# hybrid_lower_pcb3_2.net
KiCad netlist of a schematic drawn in EAGLE
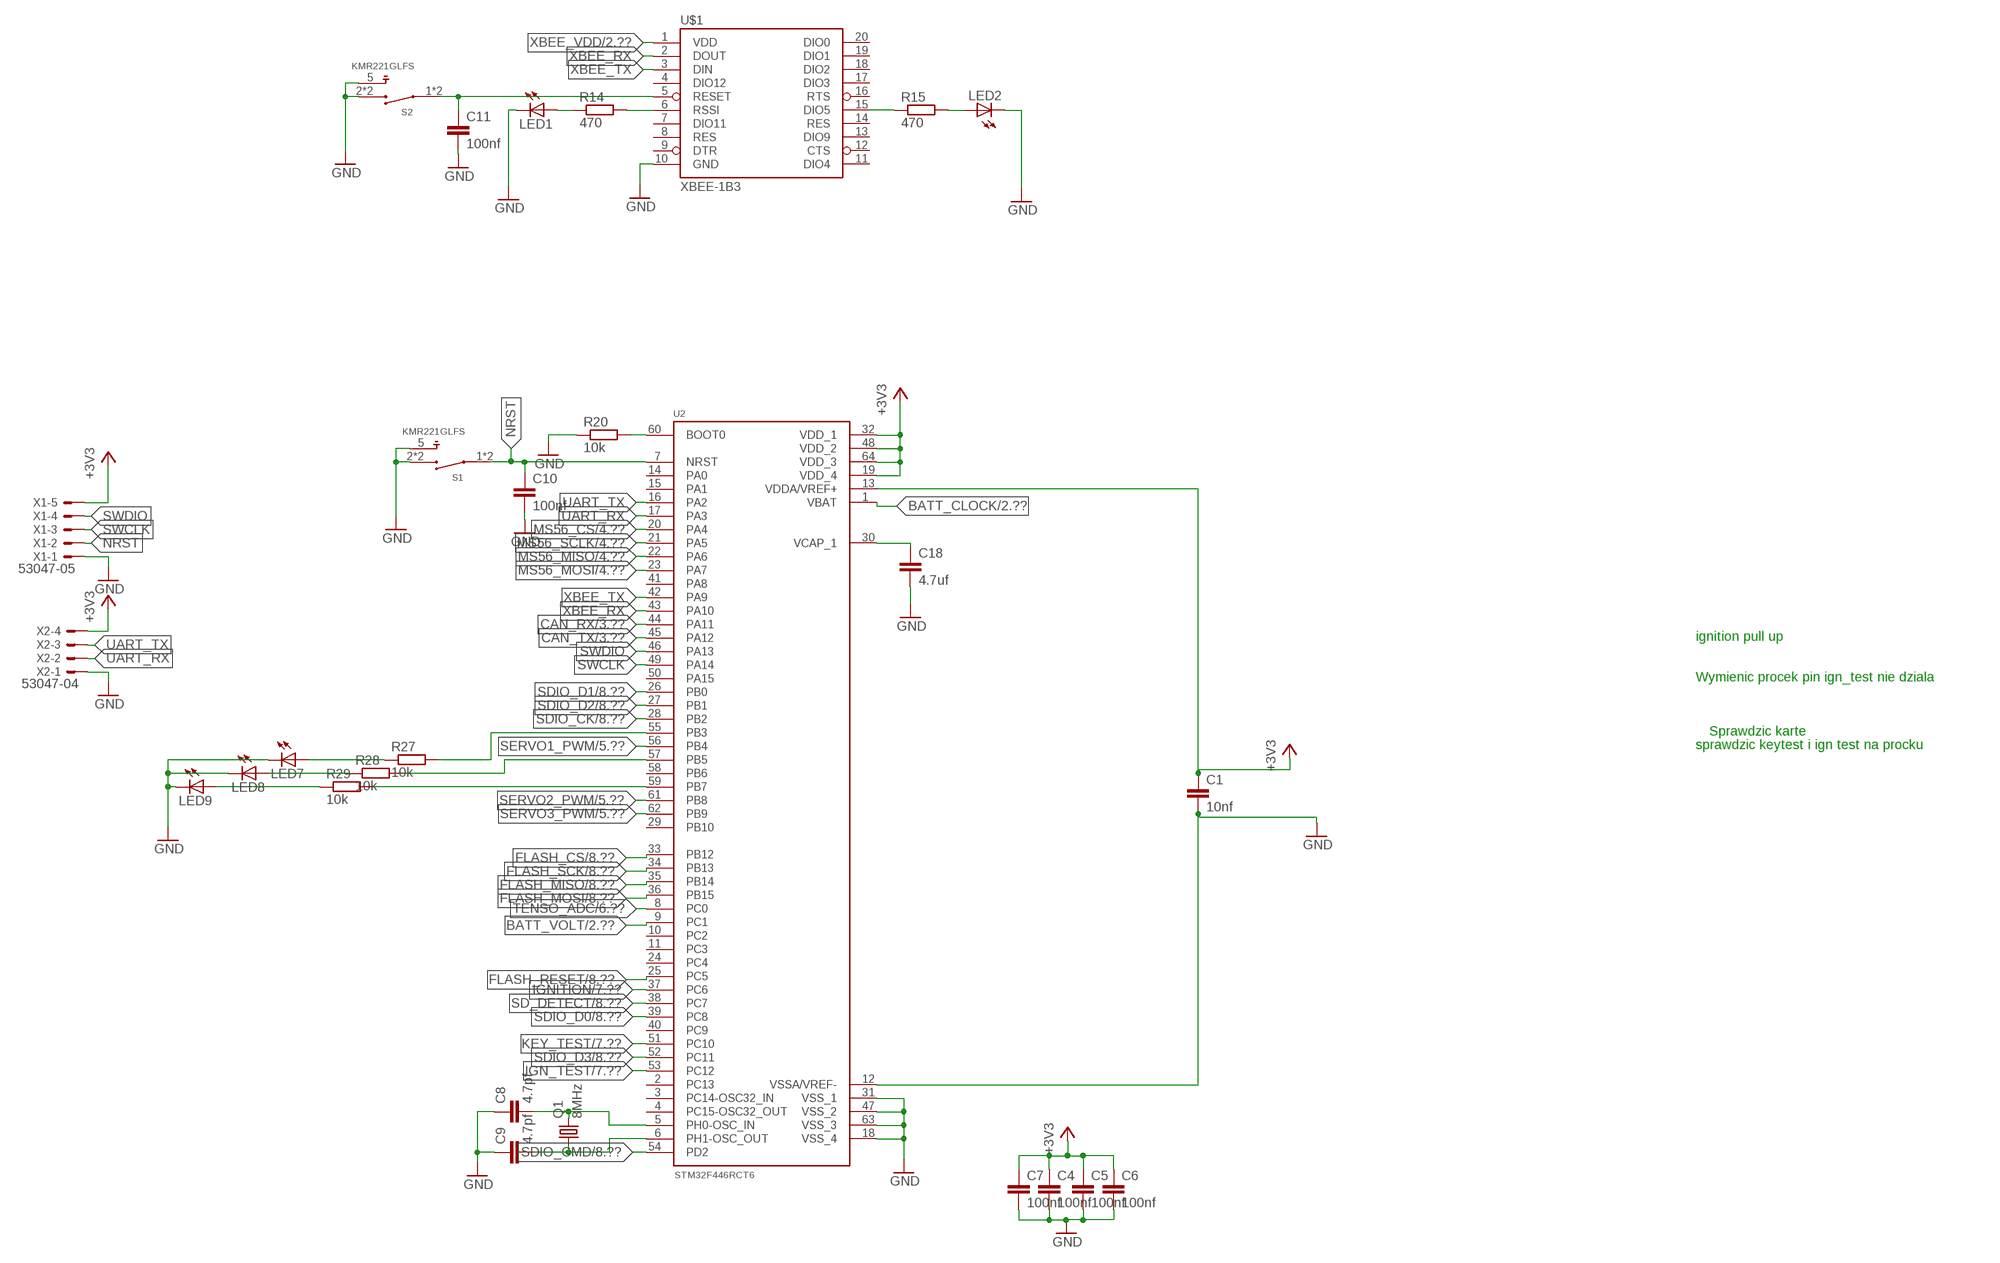
[diagram p0: schematic, sheet 1]
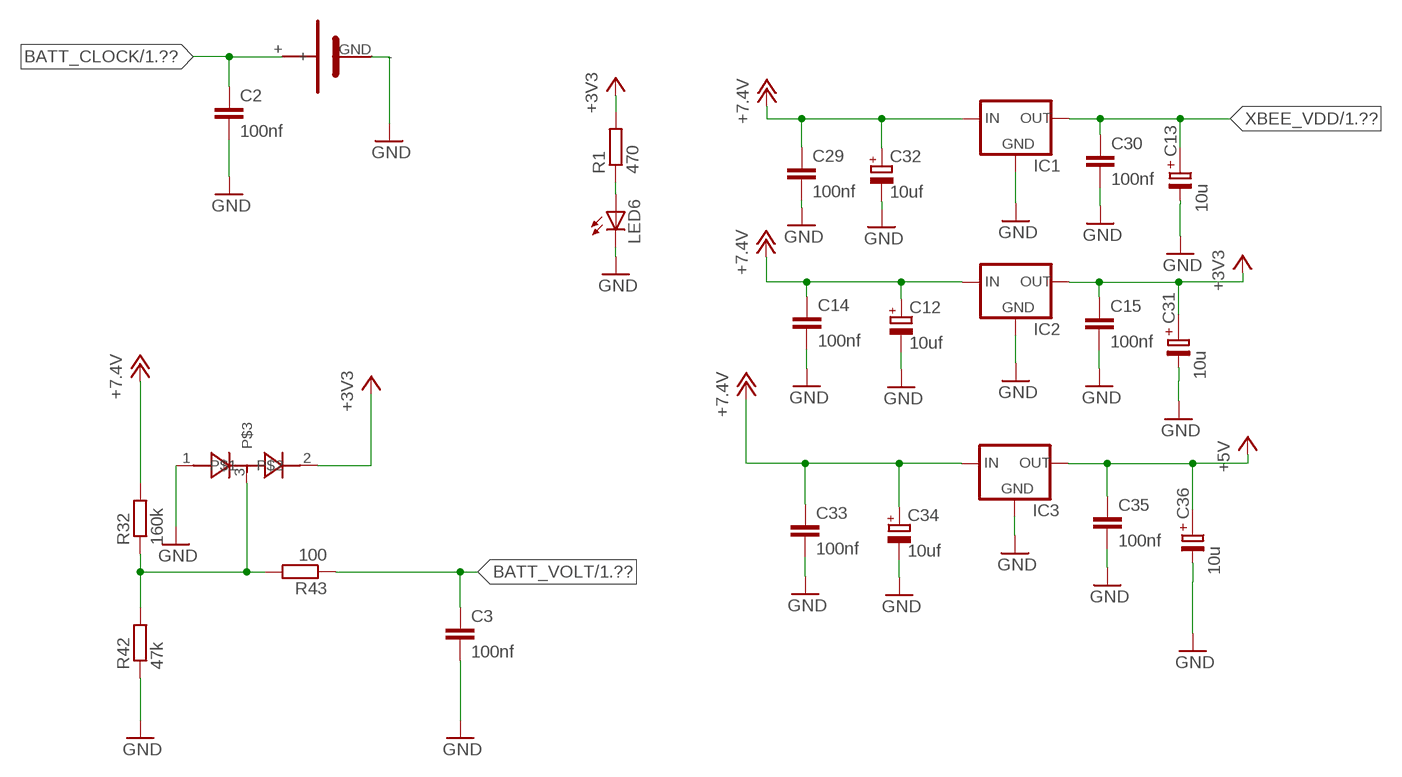
[diagram p1: schematic, sheet 2]
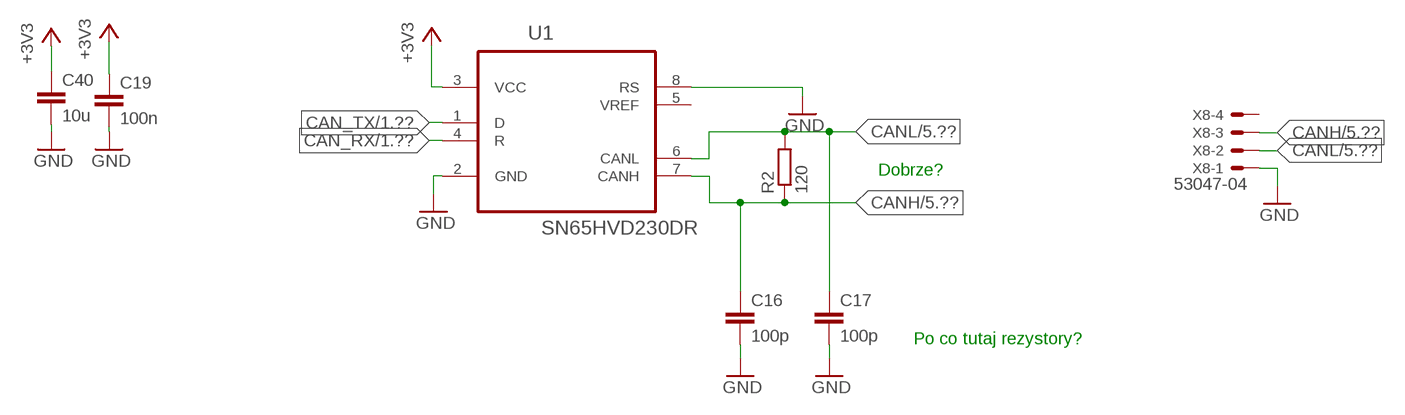
[diagram p2: schematic, sheet 3]
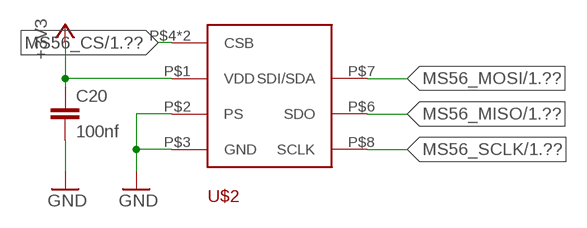
[diagram p3: schematic, sheet 4]
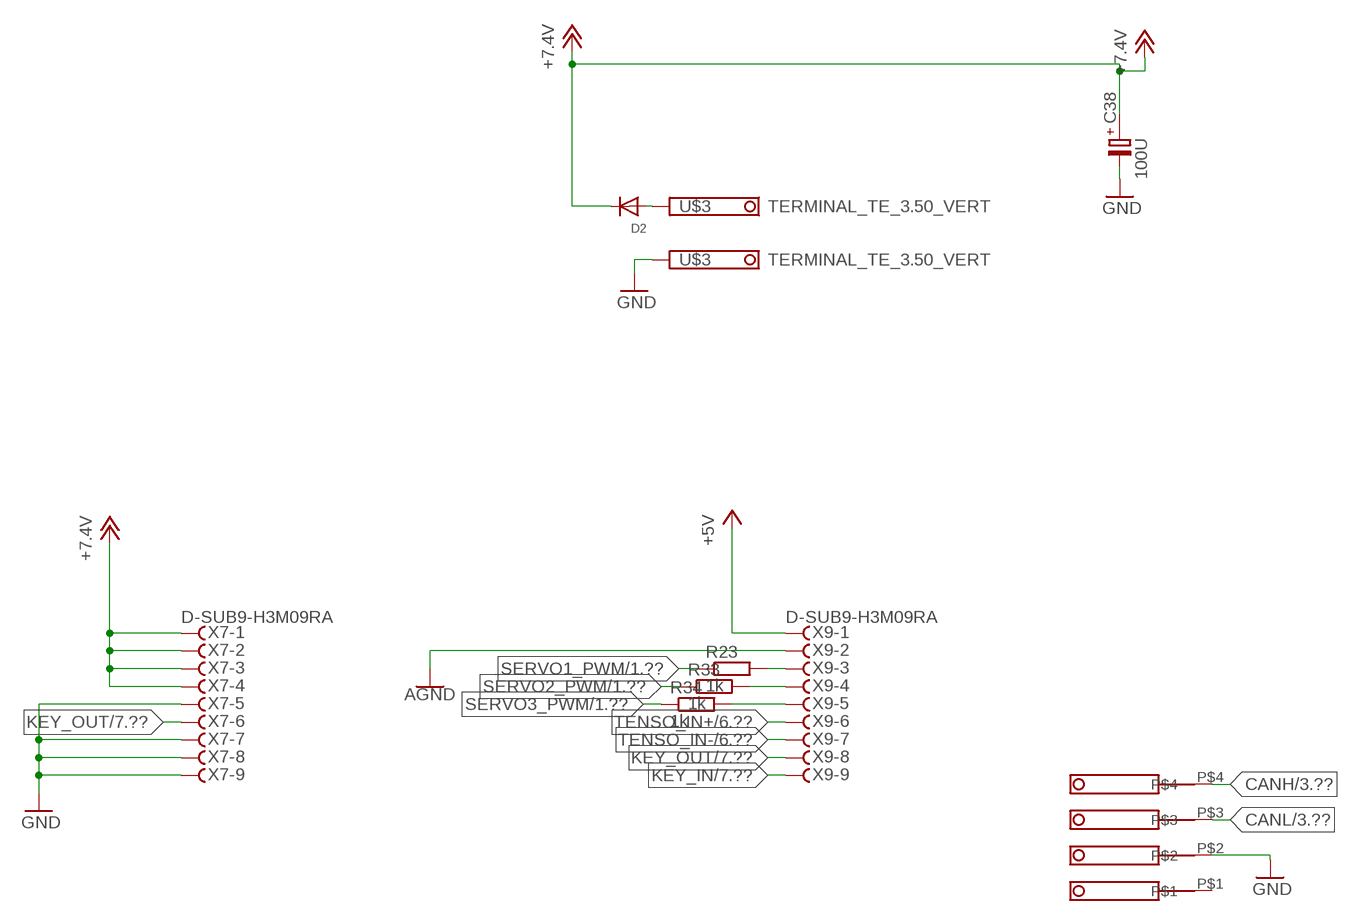
[diagram p4: schematic, sheet 5]
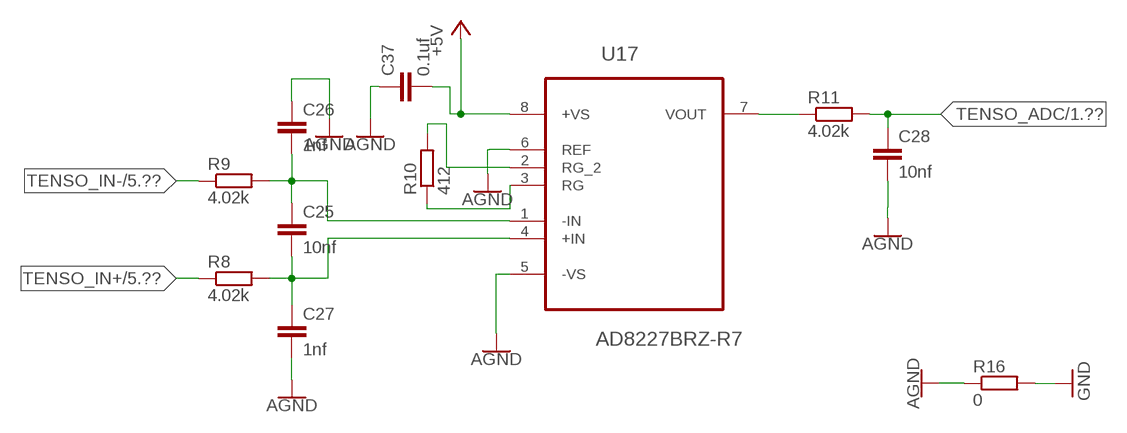
[diagram p5: schematic, sheet 6]
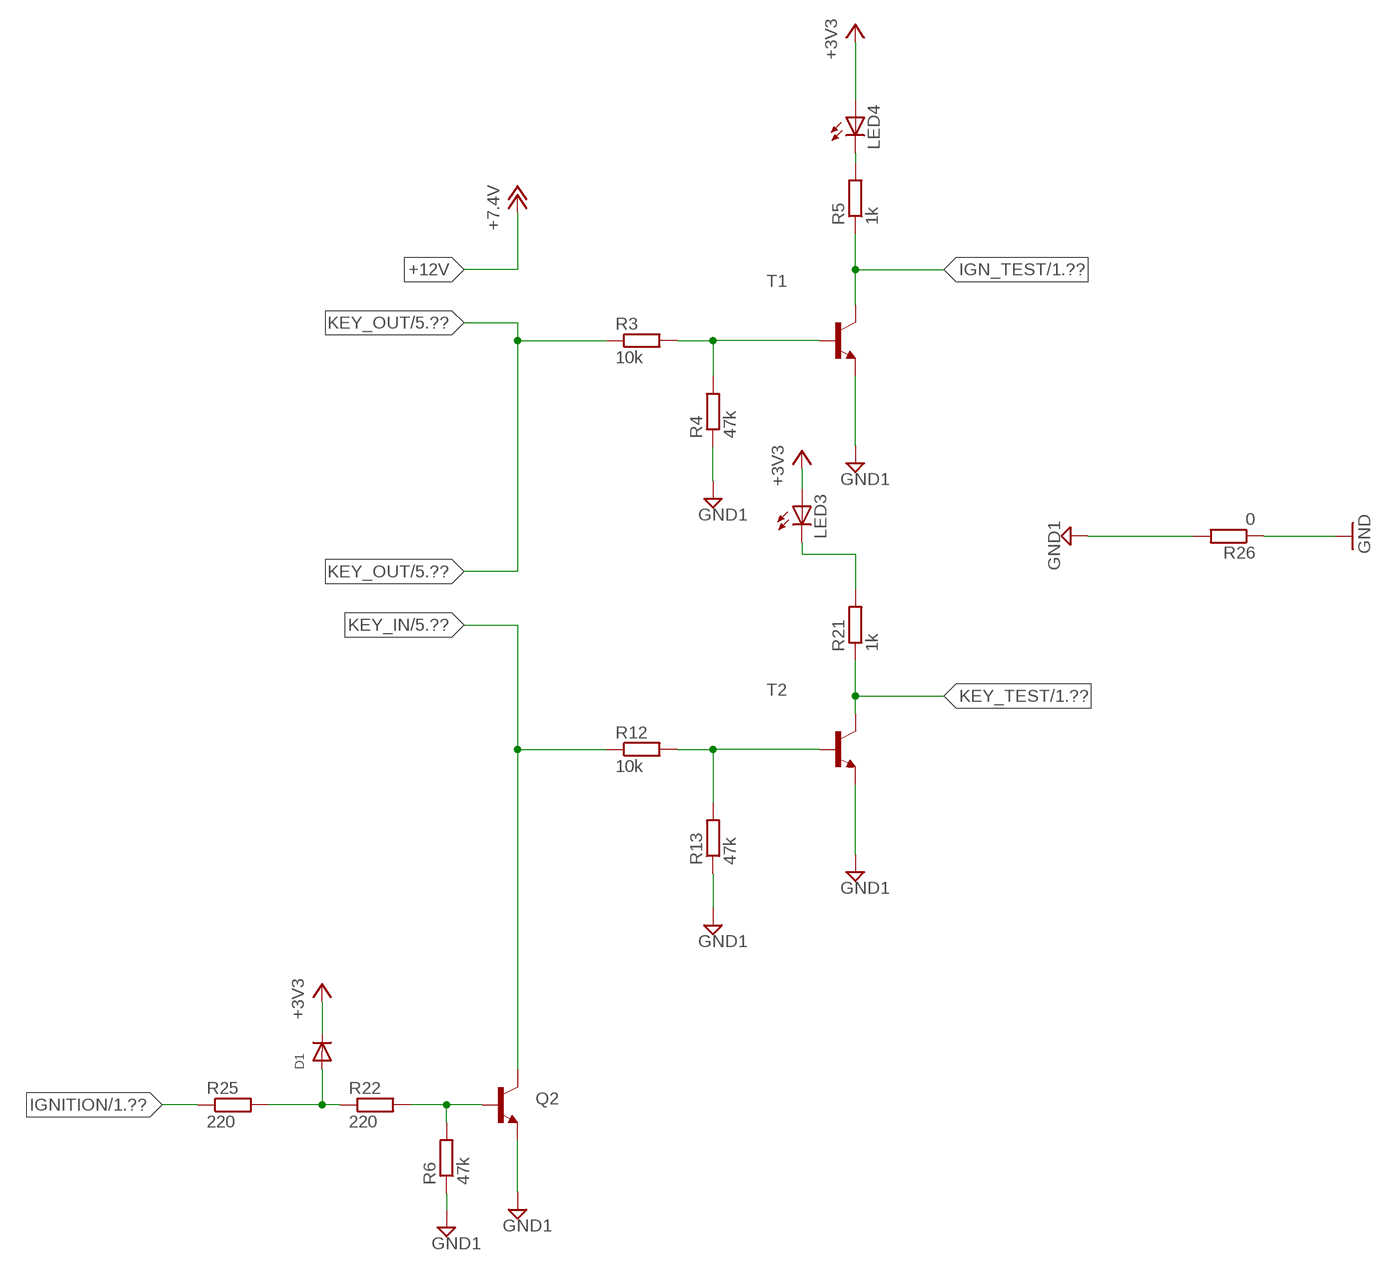
[diagram p6: schematic, sheet 7]
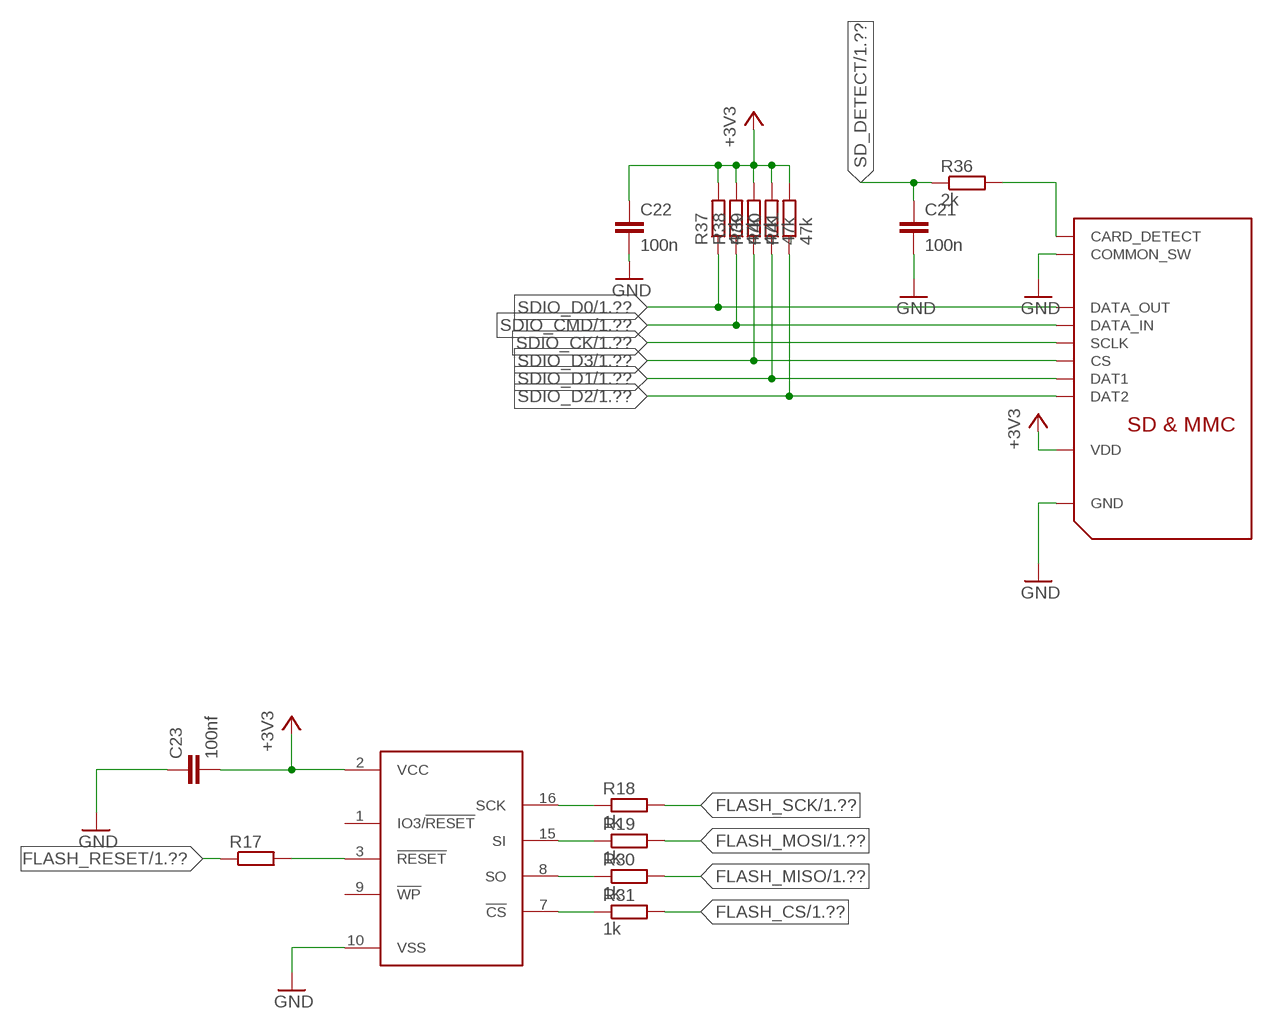
[diagram p7: schematic, sheet 8]

(export (version "E")
  (design (tool "Eeschema 10.0.6"))
  (components
    (comp (ref "C21")
      (value "100n")
      (footprint "eagle-import:C0603K")
      (libsource (lib "eagle-import") (part "C-EUC0603K"))
    )
    (comp (ref "C22")
      (value "100n")
      (footprint "eagle-import:C0603K")
      (libsource (lib "eagle-import") (part "C-EUC0603K"))
    )
    (comp (ref "C23")
      (value "100nf")
      (footprint "eagle-import:C0603")
      (libsource (lib "eagle-import") (part "rcl_334_C-EUC0603"))
    )
    (comp (ref "R17")
      (value "R-EU_R0603")
      (footprint "eagle-import:R0603")
      (libsource (lib "eagle-import") (part "rcl_334_R-EU_R0603"))
    )
    (comp (ref "R18")
      (value "1k")
      (footprint "eagle-import:R0603")
      (libsource (lib "eagle-import") (part "rcl_334_R-EU_R0603"))
    )
    (comp (ref "R19")
      (value "1k")
      (footprint "eagle-import:R0603")
      (libsource (lib "eagle-import") (part "rcl_334_R-EU_R0603"))
    )
    (comp (ref "R30")
      (value "1k")
      (footprint "eagle-import:R0603")
      (libsource (lib "eagle-import") (part "rcl_334_R-EU_R0603"))
    )
    (comp (ref "R31")
      (value "1k")
      (footprint "eagle-import:R0603")
      (libsource (lib "eagle-import") (part "rcl_334_R-EU_R0603"))
    )
    (comp (ref "R36")
      (value "2k")
      (footprint "eagle-import:R0603")
      (libsource (lib "eagle-import") (part "R-EU_R0603"))
    )
    (comp (ref "R37")
      (value "47k")
      (footprint "eagle-import:R0603")
      (libsource (lib "eagle-import") (part "R-EU_R0603"))
    )
    (comp (ref "R38")
      (value "47k")
      (footprint "eagle-import:R0603")
      (libsource (lib "eagle-import") (part "R-EU_R0603"))
    )
    (comp (ref "R39")
      (value "47k")
      (footprint "eagle-import:R0603")
      (libsource (lib "eagle-import") (part "R-EU_R0603"))
    )
    (comp (ref "R40")
      (value "47k")
      (footprint "eagle-import:R0603")
      (libsource (lib "eagle-import") (part "R-EU_R0603"))
    )
    (comp (ref "R41")
      (value "47k")
      (footprint "eagle-import:R0603")
      (libsource (lib "eagle-import") (part "R-EU_R0603"))
    )
    (comp (ref "U$11")
      (value "S25FLX")
      (footprint "eagle-import:SOIC16")
      (libsource (lib "eagle-import") (part "S25FLX"))
    )
    (comp (ref "U$16")
      (value "MOLEX_MICRO_SD_503182-1853")
      (footprint "eagle-import:MOLEX_MICRO_SD_503182-1853")
      (libsource (lib "eagle-import") (part "MOLEX_MICRO_SD_503182-1853"))
    )
    (comp (ref "D1")
      (value "DIODESOD-523")
      (footprint "eagle-import:SOD-523")
      (libsource (lib "eagle-import") (part "adafruit_420_DIODESOD-523"))
    )
    (comp (ref "LED3")
      (value "LED0603")
      (footprint "eagle-import:LED-0603")
      (libsource (lib "eagle-import") (part "LED0603"))
    )
    (comp (ref "LED4")
      (value "LED0603")
      (footprint "eagle-import:LED-0603")
      (libsource (lib "eagle-import") (part "LED0603"))
    )
    (comp (ref "Q2")
      (value "TRANSISTOR_NPNSOT23-3")
      (footprint "eagle-import:SOT23-3")
      (libsource (lib "eagle-import") (part "TRANSISTOR_NPNSOT23-3"))
    )
    (comp (ref "R3")
      (value "10k")
      (footprint "eagle-import:R0603")
      (libsource (lib "eagle-import") (part "R-EU_R0603"))
    )
    (comp (ref "R4")
      (value "47k")
      (footprint "eagle-import:R0603")
      (libsource (lib "eagle-import") (part "R-EU_R0603"))
    )
    (comp (ref "R5")
      (value "1k")
      (footprint "eagle-import:R0603")
      (libsource (lib "eagle-import") (part "R-EU_R0603"))
    )
    (comp (ref "R6")
      (value "47k")
      (footprint "eagle-import:R0603")
      (libsource (lib "eagle-import") (part "R-EU_R0603"))
    )
    (comp (ref "R12")
      (value "10k")
      (footprint "eagle-import:R0603")
      (libsource (lib "eagle-import") (part "R-EU_R0603"))
    )
    (comp (ref "R13")
      (value "47k")
      (footprint "eagle-import:R0603")
      (libsource (lib "eagle-import") (part "R-EU_R0603"))
    )
    (comp (ref "R21")
      (value "1k")
      (footprint "eagle-import:R0603")
      (libsource (lib "eagle-import") (part "R-EU_R0603"))
    )
    (comp (ref "R22")
      (value "220")
      (footprint "eagle-import:R0603")
      (libsource (lib "eagle-import") (part "R-EU_R0603"))
    )
    (comp (ref "R25")
      (value "220")
      (footprint "eagle-import:R0603")
      (libsource (lib "eagle-import") (part "R-EU_R0603"))
    )
    (comp (ref "R26")
      (value "0")
      (footprint "eagle-import:R0603")
      (libsource (lib "eagle-import") (part "R-EU_R0603"))
    )
    (comp (ref "T1")
      (value "BCW81-NPN-SOT23-BEC")
      (footprint "eagle-import:SOT23-BEC")
      (libsource (lib "eagle-import") (part "-NPN-SOT23-BECBCW81"))
    )
    (comp (ref "T2")
      (value "BCW81-NPN-SOT23-BEC")
      (footprint "eagle-import:SOT23-BEC")
      (libsource (lib "eagle-import") (part "-NPN-SOT23-BECBCW81"))
    )
    (comp (ref "C20")
      (value "100nf")
      (footprint "eagle-import:C0603")
      (libsource (lib "eagle-import") (part "resistor_C-EUC0603"))
    )
    (comp (ref "U$2")
      (value "MS56XX")
      (footprint "eagle-import:MS56XX")
      (libsource (lib "eagle-import") (part "MS56XX"))
    )
    (comp (ref "C16")
      (value "100p")
      (footprint "eagle-import:C0603")
      (libsource (lib "eagle-import") (part "C-EUC0603"))
    )
    (comp (ref "C17")
      (value "100p")
      (footprint "eagle-import:C0603")
      (libsource (lib "eagle-import") (part "C-EUC0603"))
    )
    (comp (ref "C19")
      (value "100n")
      (footprint "eagle-import:C0603")
      (libsource (lib "eagle-import") (part "C-EUC0603"))
    )
    (comp (ref "C40")
      (value "10u")
      (footprint "eagle-import:C0805")
      (libsource (lib "eagle-import") (part "C-EUC0805"))
    )
    (comp (ref "R2")
      (value "120")
      (footprint "eagle-import:R0603")
      (libsource (lib "eagle-import") (part "R-EU_R0603"))
    )
    (comp (ref "U1")
      (value "SN65HVD230DR")
      (footprint "eagle-import:SOIC127P600X175-8N")
      (fields (field (name "MF") "Texas Instruments"))
      (libsource (lib "eagle-import") (part "SN65HVD230DR"))
    )
    (comp (ref "X8")
      (value "53047-04")
      (footprint "eagle-import:53047-04")
      (fields (field (name "MF") "WALDOM/MOLEX") (field (name "MPN") "53047-0410"))
      (libsource (lib "eagle-import") (part "53?-04047"))
    )
    (comp (ref "C2")
      (value "100nf")
      (footprint "eagle-import:C0603")
      (libsource (lib "eagle-import") (part "C-EUC0603"))
    )
    (comp (ref "C3")
      (value "100nf")
      (footprint "eagle-import:C0603")
      (libsource (lib "eagle-import") (part "rcl_334_C-EUC0603"))
    )
    (comp (ref "C12")
      (value "10uf")
      (footprint "eagle-import:SANYO-OSCON_SMD_B6")
      (libsource (lib "eagle-import") (part "CPOL-EUSANYO_SMD_B6"))
    )
    (comp (ref "C13")
      (value "10u")
      (footprint "eagle-import:TE-B-3528")
      (libsource (lib "eagle-import") (part "C-PR-SMD-TE-B"))
    )
    (comp (ref "C14")
      (value "100nf")
      (footprint "eagle-import:C0603")
      (libsource (lib "eagle-import") (part "C-EUC0603"))
    )
    (comp (ref "C15")
      (value "100nf")
      (footprint "eagle-import:C0603")
      (libsource (lib "eagle-import") (part "C-EUC0603"))
    )
    (comp (ref "C29")
      (value "100nf")
      (footprint "eagle-import:C0603")
      (libsource (lib "eagle-import") (part "C-EUC0603"))
    )
    (comp (ref "C30")
      (value "100nf")
      (footprint "eagle-import:C0603")
      (libsource (lib "eagle-import") (part "C-EUC0603"))
    )
    (comp (ref "C31")
      (value "10u")
      (footprint "eagle-import:TE-B-3528")
      (libsource (lib "eagle-import") (part "C-PR-SMD-TE-B"))
    )
    (comp (ref "C32")
      (value "10uf")
      (footprint "eagle-import:SANYO-OSCON_SMD_B6")
      (libsource (lib "eagle-import") (part "CPOL-EUSANYO_SMD_B6"))
    )
    (comp (ref "C33")
      (value "100nf")
      (footprint "eagle-import:C0603")
      (libsource (lib "eagle-import") (part "C-EUC0603"))
    )
    (comp (ref "C34")
      (value "10uf")
      (footprint "eagle-import:SANYO-OSCON_SMD_B6")
      (libsource (lib "eagle-import") (part "CPOL-EUSANYO_SMD_B6"))
    )
    (comp (ref "C35")
      (value "100nf")
      (footprint "eagle-import:C0603")
      (libsource (lib "eagle-import") (part "C-EUC0603"))
    )
    (comp (ref "C36")
      (value "10u")
      (footprint "eagle-import:TE-B-3528")
      (libsource (lib "eagle-import") (part "C-PR-SMD-TE-B"))
    )
    (comp (ref "IC1")
      (value "LM1117")
      (footprint "eagle-import:SOT223")
      (libsource (lib "eagle-import") (part "LM1117"))
    )
    (comp (ref "IC2")
      (value "LM1117")
      (footprint "eagle-import:SOT223")
      (libsource (lib "eagle-import") (part "LM1117"))
    )
    (comp (ref "IC3")
      (value "LM1117")
      (footprint "eagle-import:SOT223")
      (libsource (lib "eagle-import") (part "LM1117"))
    )
    (comp (ref "LED6")
      (value "LED0603")
      (footprint "eagle-import:LED-0603")
      (libsource (lib "eagle-import") (part "LED0603"))
    )
    (comp (ref "R1")
      (value "470")
      (footprint "eagle-import:R0603")
      (libsource (lib "eagle-import") (part "resistor_R-EU_R0603"))
    )
    (comp (ref "R32")
      (value "160k")
      (footprint "eagle-import:R0603")
      (libsource (lib "eagle-import") (part "rcl_334_R-EU_R0603"))
    )
    (comp (ref "R42")
      (value "47k")
      (footprint "eagle-import:R0603")
      (libsource (lib "eagle-import") (part "rcl_334_R-EU_R0603"))
    )
    (comp (ref "R43")
      (value "100")
      (footprint "eagle-import:R0603")
      (libsource (lib "eagle-import") (part "rcl_334_R-EU_R0603"))
    )
    (comp (ref "U$13")
      (value "CR1220_POZ")
      (footprint "eagle-import:CR1220_POZ")
      (libsource (lib "eagle-import") (part "CR1220_POZ"))
    )
    (comp (ref "U$17")
      (value "BAS40W-04")
      (footprint "eagle-import:SOT65P210X110-3N")
      (libsource (lib "eagle-import") (part "BAS40W-04"))
    )
    (comp (ref "C25")
      (value "10nf")
      (footprint "eagle-import:C0603")
      (libsource (lib "eagle-import") (part "C-EUC0603"))
    )
    (comp (ref "C26")
      (value "1nf")
      (footprint "eagle-import:C0603")
      (libsource (lib "eagle-import") (part "C-EUC0603"))
    )
    (comp (ref "C27")
      (value "1nf")
      (footprint "eagle-import:C0603")
      (libsource (lib "eagle-import") (part "C-EUC0603"))
    )
    (comp (ref "C28")
      (value "10nf")
      (footprint "eagle-import:C0603")
      (libsource (lib "eagle-import") (part "C-EUC0603"))
    )
    (comp (ref "C37")
      (value "0.1uf")
      (footprint "eagle-import:C0603")
      (libsource (lib "eagle-import") (part "C-EUC0603"))
    )
    (comp (ref "R8")
      (value "4.02k")
      (footprint "eagle-import:R0603")
      (libsource (lib "eagle-import") (part "R-EU_R0603"))
    )
    (comp (ref "R9")
      (value "4.02k")
      (footprint "eagle-import:R0603")
      (libsource (lib "eagle-import") (part "R-EU_R0603"))
    )
    (comp (ref "R10")
      (value "412")
      (footprint "eagle-import:R0805")
      (libsource (lib "eagle-import") (part "R-EU_R0805"))
    )
    (comp (ref "R11")
      (value "4.02k")
      (footprint "eagle-import:R0603")
      (libsource (lib "eagle-import") (part "R-EU_R0603"))
    )
    (comp (ref "R16")
      (value "0")
      (footprint "eagle-import:R0603")
      (libsource (lib "eagle-import") (part "resistor_R-EU_R0603"))
    )
    (comp (ref "U17")
      (value "AD8227BRZ-R7")
      (footprint "eagle-import:SOIC127P600X175-8N")
      (libsource (lib "eagle-import") (part "AD8227BRZ-R7"))
    )
    (comp (ref "C38")
      (value "100U")
      (footprint "eagle-import:TE-B-3528")
      (libsource (lib "eagle-import") (part "C-PR-SMD-TE-B"))
    )
    (comp (ref "D2")
      (value "DIODESOD-523")
      (footprint "eagle-import:SOD-523")
      (libsource (lib "eagle-import") (part "DIODESOD-523"))
    )
    (comp (ref "R23")
      (value "1k")
      (footprint "eagle-import:R0603")
      (libsource (lib "eagle-import") (part "rcl_334_R-EU_R0603"))
    )
    (comp (ref "R33")
      (value "1k")
      (footprint "eagle-import:R0603")
      (libsource (lib "eagle-import") (part "rcl_334_R-EU_R0603"))
    )
    (comp (ref "R34")
      (value "1k")
      (footprint "eagle-import:R0603")
      (libsource (lib "eagle-import") (part "rcl_334_R-EU_R0603"))
    )
    (comp (ref "U$3")
      (value "TERMINAL_TE_3.50_VERT")
      (footprint "eagle-import:TE_3.5_TERMINAL_VERT")
      (libsource (lib "eagle-import") (part "TERMINAL_TE_3.50_VERT"))
    )
    (comp (ref "U$10")
      (value "39505-1005")
      (footprint "eagle-import:39505-1005")
      (libsource (lib "eagle-import") (part "39505-1005"))
    )
    (comp (ref "X7")
      (value "D-SUB9-H3M09RA")
      (footprint "eagle-import:H3M09RA")
      (libsource (lib "eagle-import") (part "D-SUB9-H3M09RA"))
    )
    (comp (ref "X9")
      (value "D-SUB9-H3M09RA")
      (footprint "eagle-import:H3M09RA")
      (libsource (lib "eagle-import") (part "D-SUB9-H3M09RA"))
    )
    (comp (ref "C1")
      (value "10nf")
      (footprint "eagle-import:C0603")
      (libsource (lib "eagle-import") (part "C-EUC0603"))
    )
    (comp (ref "C4")
      (value "100nf")
      (footprint "eagle-import:C0603")
      (libsource (lib "eagle-import") (part "C-EUC0603"))
    )
    (comp (ref "C5")
      (value "100nf")
      (footprint "eagle-import:C0603")
      (libsource (lib "eagle-import") (part "C-EUC0603"))
    )
    (comp (ref "C6")
      (value "100nf")
      (footprint "eagle-import:C0603")
      (libsource (lib "eagle-import") (part "C-EUC0603"))
    )
    (comp (ref "C7")
      (value "100nf")
      (footprint "eagle-import:C0603")
      (libsource (lib "eagle-import") (part "C-EUC0603"))
    )
    (comp (ref "C8")
      (value "4.7pf")
      (footprint "eagle-import:C0603")
      (libsource (lib "eagle-import") (part "C-EUC0603"))
    )
    (comp (ref "C9")
      (value "4.7pf")
      (footprint "eagle-import:C0603")
      (libsource (lib "eagle-import") (part "C-EUC0603"))
    )
    (comp (ref "C10")
      (value "100nf")
      (footprint "eagle-import:C0603")
      (libsource (lib "eagle-import") (part "C-EUC0603"))
    )
    (comp (ref "C11")
      (value "100nf")
      (footprint "eagle-import:C0603")
      (libsource (lib "eagle-import") (part "C-EUC0603"))
    )
    (comp (ref "C18")
      (value "4.7uf")
      (footprint "eagle-import:C0805")
      (libsource (lib "eagle-import") (part "rcl_334_C-EUC0805"))
    )
    (comp (ref "LED1")
      (value "LED0603")
      (footprint "eagle-import:LED-0603")
      (libsource (lib "eagle-import") (part "LED0603"))
    )
    (comp (ref "LED2")
      (value "LED0603")
      (footprint "eagle-import:LED-0603")
      (libsource (lib "eagle-import") (part "LED0603"))
    )
    (comp (ref "LED7")
      (value "LED0603")
      (footprint "eagle-import:LED-0603")
      (libsource (lib "eagle-import") (part "LED0603"))
    )
    (comp (ref "LED8")
      (value "LED0603")
      (footprint "eagle-import:LED-0603")
      (libsource (lib "eagle-import") (part "LED0603"))
    )
    (comp (ref "LED9")
      (value "LED0603")
      (footprint "eagle-import:LED-0603")
      (libsource (lib "eagle-import") (part "LED0603"))
    )
    (comp (ref "Q1")
      (value "8MHz")
      (footprint "eagle-import:CTS406")
      (libsource (lib "eagle-import") (part "CRYSTALCTS406"))
    )
    (comp (ref "R14")
      (value "470")
      (footprint "eagle-import:R0603")
      (libsource (lib "eagle-import") (part "R-EU_R0603"))
    )
    (comp (ref "R15")
      (value "470")
      (footprint "eagle-import:R0603")
      (libsource (lib "eagle-import") (part "R-EU_R0603"))
    )
    (comp (ref "R20")
      (value "10k")
      (footprint "eagle-import:R0603")
      (libsource (lib "eagle-import") (part "resistor_R-EU_R0603"))
    )
    (comp (ref "R27")
      (value "10k")
      (footprint "eagle-import:R0603")
      (libsource (lib "eagle-import") (part "resistor_R-EU_R0603"))
    )
    (comp (ref "R28")
      (value "10k")
      (footprint "eagle-import:R0603")
      (libsource (lib "eagle-import") (part "resistor_R-EU_R0603"))
    )
    (comp (ref "R29")
      (value "10k")
      (footprint "eagle-import:R0603")
      (libsource (lib "eagle-import") (part "resistor_R-EU_R0603"))
    )
    (comp (ref "S1")
      (value "KMR221GLFS")
      (footprint "eagle-import:SW_KMR221GLFS")
      (fields (field (name "MF") "C&K Components"))
      (libsource (lib "eagle-import") (part "KMR221GLFS"))
    )
    (comp (ref "S2")
      (value "KMR221GLFS")
      (footprint "eagle-import:SW_KMR221GLFS")
      (fields (field (name "MF") "C&K Components"))
      (libsource (lib "eagle-import") (part "KMR221GLFS"))
    )
    (comp (ref "U$1")
      (value "XBEE-1B3")
      (footprint "eagle-import:XBEE-SMD")
      (libsource (lib "eagle-import") (part "XBEE-1B3"))
    )
    (comp (ref "U2")
      (value "STM32F446RCT6")
      (footprint "eagle-import:QFP50P1200X1200X160-64N")
      (fields (field (name "MF") "STMicroelectronics"))
      (libsource (lib "eagle-import") (part "STM32F446RCT6"))
    )
    (comp (ref "X1")
      (value "53047-05")
      (footprint "eagle-import:53047-05")
      (fields (field (name "MF") "MOLEX") (field (name "MPN") "53047-0510"))
      (libsource (lib "eagle-import") (part "53?-05047"))
    )
    (comp (ref "X2")
      (value "53047-04")
      (footprint "eagle-import:53047-04")
      (fields (field (name "MF") "WALDOM/MOLEX") (field (name "MPN") "53047-0410"))
      (libsource (lib "eagle-import") (part "53?-04047"))
    )
  )
  (nets
    (net (code "1") (name "+3V3") (class "Default")
      (node (ref "C1") (pin "1") (pinfunction "1_1") (pintype "passive"))
      (node (ref "C15") (pin "1") (pinfunction "1_1") (pintype "passive"))
      (node (ref "C19") (pin "1") (pinfunction "1_1") (pintype "passive"))
      (node (ref "C20") (pin "1") (pinfunction "1_1") (pintype "passive"))
      (node (ref "C22") (pin "1") (pinfunction "1_1") (pintype "passive"))
      (node (ref "C23") (pin "2") (pinfunction "2_2") (pintype "passive"))
      (node (ref "C31") (pin "+") (pinfunction "+_+") (pintype "passive"))
      (node (ref "C4") (pin "1") (pinfunction "1_1") (pintype "passive"))
      (node (ref "C40") (pin "1") (pinfunction "1_1") (pintype "passive"))
      (node (ref "C5") (pin "1") (pinfunction "1_1") (pintype "passive"))
      (node (ref "C6") (pin "1") (pinfunction "1_1") (pintype "passive"))
      (node (ref "C7") (pin "1") (pinfunction "1_1") (pintype "passive"))
      (node (ref "D1") (pin "K") (pinfunction "C_K") (pintype "passive"))
      (node (ref "IC2") (pin "2") (pinfunction "OUT_2") (pintype "passive"))
      (node (ref "LED3") (pin "A") (pinfunction "A_A") (pintype "passive"))
      (node (ref "LED4") (pin "A") (pinfunction "A_A") (pintype "passive"))
      (node (ref "R1") (pin "2") (pinfunction "2_2") (pintype "passive"))
      (node (ref "R37") (pin "2") (pinfunction "2_2") (pintype "passive"))
      (node (ref "R38") (pin "2") (pinfunction "2_2") (pintype "passive"))
      (node (ref "R39") (pin "2") (pinfunction "2_2") (pintype "passive"))
      (node (ref "R40") (pin "2") (pinfunction "2_2") (pintype "passive"))
      (node (ref "R41") (pin "2") (pinfunction "2_2") (pintype "passive"))
      (node (ref "U$11") (pin "2") (pinfunction "VCC_2") (pintype "bidirectional"))
      (node (ref "U$16") (pin "PIN4") (pinfunction "VDD_PIN4") (pintype "power_in"))
      (node (ref "U$17") (pin "2") (pinfunction "P$2_2") (pintype "bidirectional"))
      (node (ref "U$2") (pin "P$1") (pinfunction "VDD_P$1") (pintype "bidirectional"))
      (node (ref "U1") (pin "3") (pinfunction "VCC_3") (pintype "power_in"))
      (node (ref "U2") (pin "13") (pinfunction "VDDA/VREF+_13") (pintype "power_in"))
      (node (ref "U2") (pin "19") (pinfunction "VDD_4_19") (pintype "power_in"))
      (node (ref "U2") (pin "32") (pinfunction "VDD_1_32") (pintype "power_in"))
      (node (ref "U2") (pin "48") (pinfunction "VDD_2_48") (pintype "power_in"))
      (node (ref "U2") (pin "64") (pinfunction "VDD_3_64") (pintype "power_in"))
      (node (ref "X1") (pin "5") (pinfunction "S_5") (pintype "passive"))
      (node (ref "X2") (pin "4") (pinfunction "S_4") (pintype "passive"))
    )
    (net (code "2") (name "+5V") (class "Default")
      (node (ref "C35") (pin "1") (pinfunction "1_1") (pintype "passive"))
      (node (ref "C36") (pin "+") (pinfunction "+_+") (pintype "passive"))
      (node (ref "C37") (pin "2") (pinfunction "2_2") (pintype "passive"))
      (node (ref "IC3") (pin "2") (pinfunction "OUT_2") (pintype "passive"))
      (node (ref "U17") (pin "8") (pinfunction "+VS_8") (pintype "power_in"))
      (node (ref "X9") (pin "1") (pinfunction "F_1") (pintype "passive"))
    )
    (net (code "3") (name "+12V") (class "Default")
      (node (ref "C12") (pin "+") (pinfunction "+_+") (pintype "passive"))
      (node (ref "C14") (pin "1") (pinfunction "1_1") (pintype "passive"))
      (node (ref "C29") (pin "1") (pinfunction "1_1") (pintype "passive"))
      (node (ref "C32") (pin "+") (pinfunction "+_+") (pintype "passive"))
      (node (ref "C33") (pin "1") (pinfunction "1_1") (pintype "passive"))
      (node (ref "C34") (pin "+") (pinfunction "+_+") (pintype "passive"))
      (node (ref "C38") (pin "+") (pinfunction "+_+") (pintype "passive"))
      (node (ref "D2") (pin "K") (pinfunction "C_K") (pintype "passive"))
      (node (ref "IC1") (pin "3") (pinfunction "IN_3") (pintype "input"))
      (node (ref "IC2") (pin "3") (pinfunction "IN_3") (pintype "input"))
      (node (ref "IC3") (pin "3") (pinfunction "IN_3") (pintype "input"))
      (node (ref "R32") (pin "2") (pinfunction "2_2") (pintype "passive"))
      (node (ref "X7") (pin "1") (pinfunction "F_1") (pintype "passive"))
      (node (ref "X7") (pin "2") (pinfunction "F_2") (pintype "passive"))
      (node (ref "X7") (pin "3") (pinfunction "F_3") (pintype "passive"))
      (node (ref "X7") (pin "4") (pinfunction "F_4") (pintype "passive"))
    )
    (net (code "4") (name "AGND") (class "Default")
      (node (ref "C26") (pin "1") (pinfunction "1_1") (pintype "passive"))
      (node (ref "C27") (pin "2") (pinfunction "2_2") (pintype "passive"))
      (node (ref "C28") (pin "2") (pinfunction "2_2") (pintype "passive"))
      (node (ref "C37") (pin "1") (pinfunction "1_1") (pintype "passive"))
      (node (ref "R16") (pin "1") (pinfunction "1_1") (pintype "passive"))
      (node (ref "U17") (pin "5") (pinfunction "-VS_5") (pintype "power_in"))
      (node (ref "U17") (pin "6") (pinfunction "REF_6") (pintype "input"))
      (node (ref "X9") (pin "2") (pinfunction "F_2") (pintype "passive"))
    )
    (net (code "5") (name "BATT_CLOCK") (class "Default")
      (node (ref "C2") (pin "1") (pinfunction "1_1") (pintype "passive"))
      (node (ref "U$13") (pin "+") (pinfunction "+_+") (pintype "bidirectional"))
      (node (ref "U2") (pin "1") (pinfunction "VBAT_1") (pintype "power_in"))
    )
    (net (code "6") (name "BATT_VOLT") (class "Default")
      (node (ref "C3") (pin "1") (pinfunction "1_1") (pintype "passive"))
      (node (ref "R43") (pin "1") (pinfunction "1_1") (pintype "passive"))
      (node (ref "U2") (pin "9") (pinfunction "PC1_9") (pintype "bidirectional"))
    )
    (net (code "7") (name "CANH") (class "Default")
      (node (ref "C16") (pin "1") (pinfunction "1_1") (pintype "passive"))
      (node (ref "R2") (pin "1") (pinfunction "1_1") (pintype "passive"))
      (node (ref "U$10") (pin "P$4") (pinfunction "P$4_P$4") (pintype "bidirectional"))
      (node (ref "U1") (pin "7") (pinfunction "CANH_7") (pintype "output"))
      (node (ref "X8") (pin "3") (pinfunction "S_3") (pintype "passive"))
    )
    (net (code "8") (name "CANL") (class "Default")
      (node (ref "C17") (pin "1") (pinfunction "1_1") (pintype "passive"))
      (node (ref "R2") (pin "2") (pinfunction "2_2") (pintype "passive"))
      (node (ref "U$10") (pin "P$3") (pinfunction "P$3_P$3") (pintype "bidirectional"))
      (node (ref "U1") (pin "6") (pinfunction "CANL_6") (pintype "output"))
      (node (ref "X8") (pin "2") (pinfunction "S_2") (pintype "passive"))
    )
    (net (code "9") (name "CAN_RX") (class "Default")
      (node (ref "U1") (pin "4") (pinfunction "R_4") (pintype "output"))
      (node (ref "U2") (pin "44") (pinfunction "PA11_44") (pintype "bidirectional"))
    )
    (net (code "10") (name "CAN_TX") (class "Default")
      (node (ref "U1") (pin "1") (pinfunction "D_1") (pintype "input"))
      (node (ref "U2") (pin "45") (pinfunction "PA12_45") (pintype "bidirectional"))
    )
    (net (code "11") (name "FLASH_CS") (class "Default")
      (node (ref "R31") (pin "2") (pinfunction "2_2") (pintype "passive"))
      (node (ref "U2") (pin "33") (pinfunction "PB12_33") (pintype "bidirectional"))
    )
    (net (code "12") (name "FLASH_MISO") (class "Default")
      (node (ref "R30") (pin "2") (pinfunction "2_2") (pintype "passive"))
      (node (ref "U2") (pin "35") (pinfunction "PB14_35") (pintype "bidirectional"))
    )
    (net (code "13") (name "FLASH_MOSI") (class "Default")
      (node (ref "R19") (pin "2") (pinfunction "2_2") (pintype "passive"))
      (node (ref "U2") (pin "36") (pinfunction "PB15_36") (pintype "bidirectional"))
    )
    (net (code "14") (name "FLASH_RESET") (class "Default")
      (node (ref "R17") (pin "1") (pinfunction "1_1") (pintype "passive"))
      (node (ref "U2") (pin "25") (pinfunction "PC5_25") (pintype "bidirectional"))
    )
    (net (code "15") (name "FLASH_SCK") (class "Default")
      (node (ref "R18") (pin "2") (pinfunction "2_2") (pintype "passive"))
      (node (ref "U2") (pin "34") (pinfunction "PB13_34") (pintype "bidirectional"))
    )
    (net (code "16") (name "GND") (class "Default")
      (node (ref "C1") (pin "2") (pinfunction "2_2") (pintype "passive"))
      (node (ref "C10") (pin "2") (pinfunction "2_2") (pintype "passive"))
      (node (ref "C11") (pin "2") (pinfunction "2_2") (pintype "passive"))
      (node (ref "C12") (pin "-") (pinfunction "-_-") (pintype "passive"))
      (node (ref "C13") (pin "-") (pinfunction "-_-") (pintype "passive"))
      (node (ref "C14") (pin "2") (pinfunction "2_2") (pintype "passive"))
      (node (ref "C15") (pin "2") (pinfunction "2_2") (pintype "passive"))
      (node (ref "C16") (pin "2") (pinfunction "2_2") (pintype "passive"))
      (node (ref "C17") (pin "2") (pinfunction "2_2") (pintype "passive"))
      (node (ref "C18") (pin "2") (pinfunction "2_2") (pintype "passive"))
      (node (ref "C19") (pin "2") (pinfunction "2_2") (pintype "passive"))
      (node (ref "C2") (pin "2") (pinfunction "2_2") (pintype "passive"))
      (node (ref "C20") (pin "2") (pinfunction "2_2") (pintype "passive"))
      (node (ref "C21") (pin "2") (pinfunction "2_2") (pintype "passive"))
      (node (ref "C22") (pin "2") (pinfunction "2_2") (pintype "passive"))
      (node (ref "C23") (pin "1") (pinfunction "1_1") (pintype "passive"))
      (node (ref "C29") (pin "2") (pinfunction "2_2") (pintype "passive"))
      (node (ref "C3") (pin "2") (pinfunction "2_2") (pintype "passive"))
      (node (ref "C30") (pin "2") (pinfunction "2_2") (pintype "passive"))
      (node (ref "C31") (pin "-") (pinfunction "-_-") (pintype "passive"))
      (node (ref "C32") (pin "-") (pinfunction "-_-") (pintype "passive"))
      (node (ref "C33") (pin "2") (pinfunction "2_2") (pintype "passive"))
      (node (ref "C34") (pin "-") (pinfunction "-_-") (pintype "passive"))
      (node (ref "C35") (pin "2") (pinfunction "2_2") (pintype "passive"))
      (node (ref "C36") (pin "-") (pinfunction "-_-") (pintype "passive"))
      (node (ref "C38") (pin "-") (pinfunction "-_-") (pintype "passive"))
      (node (ref "C4") (pin "2") (pinfunction "2_2") (pintype "passive"))
      (node (ref "C40") (pin "2") (pinfunction "2_2") (pintype "passive"))
      (node (ref "C5") (pin "2") (pinfunction "2_2") (pintype "passive"))
      (node (ref "C6") (pin "2") (pinfunction "2_2") (pintype "passive"))
      (node (ref "C7") (pin "2") (pinfunction "2_2") (pintype "passive"))
      (node (ref "C8") (pin "1") (pinfunction "1_1") (pintype "passive"))
      (node (ref "C9") (pin "1") (pinfunction "1_1") (pintype "passive"))
      (node (ref "IC1") (pin "1") (pinfunction "GND_1") (pintype "input"))
      (node (ref "IC2") (pin "1") (pinfunction "GND_1") (pintype "input"))
      (node (ref "IC3") (pin "1") (pinfunction "GND_1") (pintype "input"))
      (node (ref "LED1") (pin "C") (pinfunction "C_C") (pintype "passive"))
      (node (ref "LED2") (pin "C") (pinfunction "C_C") (pintype "passive"))
      (node (ref "LED6") (pin "C") (pinfunction "C_C") (pintype "passive"))
      (node (ref "LED7") (pin "C") (pinfunction "C_C") (pintype "passive"))
      (node (ref "LED8") (pin "C") (pinfunction "C_C") (pintype "passive"))
      (node (ref "LED9") (pin "C") (pinfunction "C_C") (pintype "passive"))
      (node (ref "R16") (pin "2") (pinfunction "2_2") (pintype "passive"))
      (node (ref "R20") (pin "1") (pinfunction "1_1") (pintype "passive"))
      (node (ref "R26") (pin "1") (pinfunction "1_1") (pintype "passive"))
      (node (ref "R42") (pin "1") (pinfunction "1_1") (pintype "passive"))
      (node (ref "S1") (pin "2") (pinfunction "3_2") (pintype "passive"))
      (node (ref "S1") (pin "3") (pinfunction "3_3") (pintype "passive"))
      (node (ref "S1") (pin "5") (pinfunction "5_5") (pintype "passive"))
      (node (ref "S2") (pin "2") (pinfunction "3_2") (pintype "passive"))
      (node (ref "S2") (pin "3") (pinfunction "3_3") (pintype "passive"))
      (node (ref "S2") (pin "5") (pinfunction "5_5") (pintype "passive"))
      (node (ref "U$1") (pin "10") (pinfunction "GND_10") (pintype "power_in"))
      (node (ref "U$10") (pin "P$2") (pinfunction "P$2_P$2") (pintype "bidirectional"))
      (node (ref "U$11") (pin "10") (pinfunction "VSS_10") (pintype "bidirectional"))
      (node (ref "U$13") (pin "GND") (pinfunction "-_GND") (pintype "bidirectional"))
      (node (ref "U$16") (pin "DETECT_GND") (pinfunction "COMMON_SW_DETECT_GND") (pintype "passive"))
      (node (ref "U$16") (pin "PIN6") (pinfunction "GND_PIN6") (pintype "power_in"))
      (node (ref "U$17") (pin "1") (pinfunction "P$1_1") (pintype "bidirectional"))
      (node (ref "U$2") (pin "P$2") (pinfunction "PS_P$2") (pintype "bidirectional"))
      (node (ref "U$2") (pin "P$3") (pinfunction "GND_P$3") (pintype "bidirectional"))
      (node (ref "U$3") (pin "P$2") (pinfunction "K1_P$2") (pintype "passive"))
      (node (ref "U1") (pin "2") (pinfunction "GND_2") (pintype "passive"))
      (node (ref "U1") (pin "8") (pinfunction "RS_8") (pintype "input"))
      (node (ref "U2") (pin "12") (pinfunction "VSSA/VREF-_12") (pintype "power_in"))
      (node (ref "U2") (pin "18") (pinfunction "VSS_4_18") (pintype "power_in"))
      (node (ref "U2") (pin "31") (pinfunction "VSS_1_31") (pintype "power_in"))
      (node (ref "U2") (pin "47") (pinfunction "VSS_2_47") (pintype "power_in"))
      (node (ref "U2") (pin "63") (pinfunction "VSS_3_63") (pintype "power_in"))
      (node (ref "X1") (pin "1") (pinfunction "S_1") (pintype "passive"))
      (node (ref "X2") (pin "1") (pinfunction "S_1") (pintype "passive"))
      (node (ref "X7") (pin "5") (pinfunction "F_5") (pintype "passive"))
      (node (ref "X7") (pin "7") (pinfunction "F_7") (pintype "passive"))
      (node (ref "X7") (pin "8") (pinfunction "F_8") (pintype "passive"))
      (node (ref "X7") (pin "9") (pinfunction "F_9") (pintype "passive"))
      (node (ref "X8") (pin "1") (pinfunction "S_1") (pintype "passive"))
    )
    (net (code "17") (name "GND1") (class "Default")
      (node (ref "Q2") (pin "2") (pinfunction "E_2") (pintype "passive"))
      (node (ref "R13") (pin "1") (pinfunction "1_1") (pintype "passive"))
      (node (ref "R26") (pin "2") (pinfunction "2_2") (pintype "passive"))
      (node (ref "R4") (pin "1") (pinfunction "1_1") (pintype "passive"))
      (node (ref "R6") (pin "1") (pinfunction "1_1") (pintype "passive"))
      (node (ref "T1") (pin "E") (pinfunction "E_E") (pintype "passive"))
      (node (ref "T2") (pin "E") (pinfunction "E_E") (pintype "passive"))
    )
    (net (code "18") (name "IGNITION") (class "Default")
      (node (ref "R25") (pin "1") (pinfunction "1_1") (pintype "passive"))
      (node (ref "U2") (pin "37") (pinfunction "PC6_37") (pintype "bidirectional"))
    )
    (net (code "19") (name "IGN_TEST") (class "Default")
      (node (ref "R5") (pin "1") (pinfunction "1_1") (pintype "passive"))
      (node (ref "T1") (pin "C") (pinfunction "C_C") (pintype "passive"))
      (node (ref "U2") (pin "53") (pinfunction "PC12_53") (pintype "bidirectional"))
    )
    (net (code "20") (name "KEY_IN") (class "Default")
      (node (ref "Q2") (pin "3") (pinfunction "C_3") (pintype "passive"))
      (node (ref "R12") (pin "1") (pinfunction "1_1") (pintype "passive"))
      (node (ref "X9") (pin "9") (pinfunction "F_9") (pintype "passive"))
    )
    (net (code "21") (name "KEY_OUT") (class "Default")
      (node (ref "R3") (pin "1") (pinfunction "1_1") (pintype "passive"))
      (node (ref "X7") (pin "6") (pinfunction "F_6") (pintype "passive"))
      (node (ref "X9") (pin "8") (pinfunction "F_8") (pintype "passive"))
    )
    (net (code "22") (name "KEY_TEST") (class "Default")
      (node (ref "R21") (pin "1") (pinfunction "1_1") (pintype "passive"))
      (node (ref "T2") (pin "C") (pinfunction "C_C") (pintype "passive"))
      (node (ref "U2") (pin "51") (pinfunction "PC10_51") (pintype "bidirectional"))
    )
    (net (code "23") (name "MS56_CS") (class "Default")
      (node (ref "U$2") (pin "P$4") (pinfunction "CSB_P$4") (pintype "bidirectional"))
      (node (ref "U$2") (pin "P$5") (pinfunction "CSB_P$5") (pintype "bidirectional"))
      (node (ref "U2") (pin "20") (pinfunction "PA4_20") (pintype "bidirectional"))
    )
    (net (code "24") (name "MS56_MISO") (class "Default")
      (node (ref "U$2") (pin "P$6") (pinfunction "SDO_P$6") (pintype "bidirectional"))
      (node (ref "U2") (pin "22") (pinfunction "PA6_22") (pintype "bidirectional"))
    )
    (net (code "25") (name "MS56_MOSI") (class "Default")
      (node (ref "U$2") (pin "P$7") (pinfunction "SDI/SDA_P$7") (pintype "bidirectional"))
      (node (ref "U2") (pin "23") (pinfunction "PA7_23") (pintype "bidirectional"))
    )
    (net (code "26") (name "MS56_SCLK") (class "Default")
      (node (ref "U$2") (pin "P$8") (pinfunction "SCLK_P$8") (pintype "bidirectional"))
      (node (ref "U2") (pin "21") (pinfunction "PA5_21") (pintype "bidirectional"))
    )
    (net (code "27") (name "NRST") (class "Default")
      (node (ref "C10") (pin "1") (pinfunction "1_1") (pintype "passive"))
      (node (ref "S1") (pin "1") (pinfunction "1_1") (pintype "passive"))
      (node (ref "S1") (pin "4") (pinfunction "1_4") (pintype "passive"))
      (node (ref "U2") (pin "7") (pinfunction "NRST_7") (pintype "bidirectional"))
      (node (ref "X1") (pin "2") (pinfunction "S_2") (pintype "passive"))
    )
    (net (code "28") (name "Net-(D1-PadA)") (class "Default")
      (node (ref "D1") (pin "A") (pinfunction "A_A") (pintype "passive"))
      (node (ref "R22") (pin "1") (pinfunction "1_1") (pintype "passive"))
      (node (ref "R25") (pin "2") (pinfunction "2_2") (pintype "passive"))
    )
    (net (code "29") (name "Net-(LED1-PadA)") (class "Default")
      (node (ref "LED1") (pin "A") (pinfunction "A_A") (pintype "passive"))
      (node (ref "R14") (pin "1") (pinfunction "1_1") (pintype "passive"))
    )
    (net (code "30") (name "Net-(LED2-PadA)") (class "Default")
      (node (ref "LED2") (pin "A") (pinfunction "A_A") (pintype "passive"))
      (node (ref "R15") (pin "2") (pinfunction "2_2") (pintype "passive"))
    )
    (net (code "31") (name "Net-(LED3-PadC)") (class "Default")
      (node (ref "LED3") (pin "C") (pinfunction "C_C") (pintype "passive"))
      (node (ref "R21") (pin "2") (pinfunction "2_2") (pintype "passive"))
    )
    (net (code "32") (name "Net-(LED4-PadC)") (class "Default")
      (node (ref "LED4") (pin "C") (pinfunction "C_C") (pintype "passive"))
      (node (ref "R5") (pin "2") (pinfunction "2_2") (pintype "passive"))
    )
    (net (code "33") (name "Net-(LED6-PadA)") (class "Default")
      (node (ref "LED6") (pin "A") (pinfunction "A_A") (pintype "passive"))
      (node (ref "R1") (pin "1") (pinfunction "1_1") (pintype "passive"))
    )
    (net (code "34") (name "Net-(LED7-PadA)") (class "Default")
      (node (ref "LED7") (pin "A") (pinfunction "A_A") (pintype "passive"))
      (node (ref "R27") (pin "1") (pinfunction "1_1") (pintype "passive"))
    )
    (net (code "35") (name "Net-(LED8-PadA)") (class "Default")
      (node (ref "LED8") (pin "A") (pinfunction "A_A") (pintype "passive"))
      (node (ref "R28") (pin "1") (pinfunction "1_1") (pintype "passive"))
    )
    (net (code "36") (name "Net-(LED9-PadA)") (class "Default")
      (node (ref "LED9") (pin "A") (pinfunction "A_A") (pintype "passive"))
      (node (ref "R29") (pin "1") (pinfunction "1_1") (pintype "passive"))
    )
    (net (code "37") (name "Net-(Q1-2)") (class "Default")
      (node (ref "C8") (pin "2") (pinfunction "2_2") (pintype "passive"))
      (node (ref "Q1") (pin "3") (pinfunction "2_3") (pintype "passive"))
      (node (ref "U2") (pin "5") (pinfunction "PH0-OSC_IN_5") (pintype "bidirectional"))
    )
    (net (code "38") (name "Net-(Q2-B)") (class "Default")
      (node (ref "Q2") (pin "1") (pinfunction "B_1") (pintype "passive"))
      (node (ref "R22") (pin "2") (pinfunction "2_2") (pintype "passive"))
      (node (ref "R6") (pin "2") (pinfunction "2_2") (pintype "passive"))
    )
    (net (code "39") (name "Net-(R3-Pad2)") (class "Default")
      (node (ref "R3") (pin "2") (pinfunction "2_2") (pintype "passive"))
      (node (ref "R4") (pin "2") (pinfunction "2_2") (pintype "passive"))
      (node (ref "T1") (pin "B") (pinfunction "B_B") (pintype "passive"))
    )
    (net (code "40") (name "Net-(R12-Pad2)") (class "Default")
      (node (ref "R12") (pin "2") (pinfunction "2_2") (pintype "passive"))
      (node (ref "R13") (pin "2") (pinfunction "2_2") (pintype "passive"))
      (node (ref "T2") (pin "B") (pinfunction "B_B") (pintype "passive"))
    )
    (net (code "41") (name "Net-(U$1-DIO5)") (class "Default")
      (node (ref "R15") (pin "1") (pinfunction "1_1") (pintype "passive"))
      (node (ref "U$1") (pin "15") (pinfunction "DIO5_15") (pintype "bidirectional"))
    )
    (net (code "42") (name "Net-(U$1-RESET)") (class "Default")
      (node (ref "C11") (pin "1") (pinfunction "1_1") (pintype "passive"))
      (node (ref "S2") (pin "1") (pinfunction "1_1") (pintype "passive"))
      (node (ref "S2") (pin "4") (pinfunction "1_4") (pintype "passive"))
      (node (ref "U$1") (pin "5") (pinfunction "RESET_5") (pintype "input"))
    )
    (net (code "43") (name "Net-(U$1-RSSI)") (class "Default")
      (node (ref "R14") (pin "2") (pinfunction "2_2") (pintype "passive"))
      (node (ref "U$1") (pin "6") (pinfunction "RSSI_6") (pintype "bidirectional"))
    )
    (net (code "44") (name "Net-(U$3-K)") (class "Default")
      (node (ref "D2") (pin "A") (pinfunction "A_A") (pintype "passive"))
      (node (ref "U$3") (pin "P$1") (pinfunction "K_P$1") (pintype "passive"))
    )
    (net (code "45") (name "Net-(U$11-SCK)") (class "Default")
      (node (ref "R18") (pin "1") (pinfunction "1_1") (pintype "passive"))
      (node (ref "U$11") (pin "16") (pinfunction "SCK_16") (pintype "bidirectional"))
    )
    (net (code "46") (name "Net-(U$11-SI)") (class "Default")
      (node (ref "R19") (pin "1") (pinfunction "1_1") (pintype "passive"))
      (node (ref "U$11") (pin "15") (pinfunction "SI_15") (pintype "bidirectional"))
    )
    (net (code "47") (name "Net-(U$11-SO)") (class "Default")
      (node (ref "R30") (pin "1") (pinfunction "1_1") (pintype "passive"))
      (node (ref "U$11") (pin "8") (pinfunction "SO_8") (pintype "bidirectional"))
    )
    (net (code "48") (name "Net-(U$11-~{CS})") (class "Default")
      (node (ref "R31") (pin "1") (pinfunction "1_1") (pintype "passive"))
      (node (ref "U$11") (pin "7") (pinfunction "~{CS}_7") (pintype "bidirectional"))
    )
    (net (code "49") (name "Net-(U$11-~{RESET})") (class "Default")
      (node (ref "R17") (pin "2") (pinfunction "2_2") (pintype "passive"))
      (node (ref "U$11") (pin "3") (pinfunction "~{RESET}_3") (pintype "bidirectional"))
    )
    (net (code "50") (name "Net-(U$16-CARD_DETECT)") (class "Default")
      (node (ref "R36") (pin "2") (pinfunction "2_2") (pintype "passive"))
      (node (ref "U$16") (pin "DETECT") (pinfunction "CARD_DETECT_DETECT") (pintype "passive"))
    )
    (net (code "51") (name "Net-(U$17-P$3)") (class "Default")
      (node (ref "R32") (pin "1") (pinfunction "1_1") (pintype "passive"))
      (node (ref "R42") (pin "2") (pinfunction "2_2") (pintype "passive"))
      (node (ref "R43") (pin "2") (pinfunction "2_2") (pintype "passive"))
      (node (ref "U$17") (pin "3") (pinfunction "P$3_3") (pintype "bidirectional"))
    )
    (net (code "52") (name "Net-(U2-BOOT0)") (class "Default")
      (node (ref "R20") (pin "2") (pinfunction "2_2") (pintype "passive"))
      (node (ref "U2") (pin "60") (pinfunction "BOOT0_60") (pintype "input"))
    )
    (net (code "53") (name "Net-(U2-PB3)") (class "Default")
      (node (ref "R27") (pin "2") (pinfunction "2_2") (pintype "passive"))
      (node (ref "U2") (pin "55") (pinfunction "PB3_55") (pintype "bidirectional"))
    )
    (net (code "54") (name "Net-(U2-PB5)") (class "Default")
      (node (ref "R28") (pin "2") (pinfunction "2_2") (pintype "passive"))
      (node (ref "U2") (pin "57") (pinfunction "PB5_57") (pintype "bidirectional"))
    )
    (net (code "55") (name "Net-(U2-PB7)") (class "Default")
      (node (ref "R29") (pin "2") (pinfunction "2_2") (pintype "passive"))
      (node (ref "U2") (pin "59") (pinfunction "PB7_59") (pintype "bidirectional"))
    )
    (net (code "56") (name "Net-(U2-PH1-OSC_OUT)") (class "Default")
      (node (ref "C9") (pin "2") (pinfunction "2_2") (pintype "passive"))
      (node (ref "Q1") (pin "1") (pinfunction "1_1") (pintype "passive"))
      (node (ref "U2") (pin "6") (pinfunction "PH1-OSC_OUT_6") (pintype "bidirectional"))
    )
    (net (code "57") (name "Net-(U2-VCAP_1)") (class "Default")
      (node (ref "C18") (pin "1") (pinfunction "1_1") (pintype "passive"))
      (node (ref "U2") (pin "30") (pinfunction "VCAP_1_30") (pintype "power_in"))
    )
    (net (code "58") (name "Net-(U17-+IN)") (class "Default")
      (node (ref "C25") (pin "2") (pinfunction "2_2") (pintype "passive"))
      (node (ref "C27") (pin "1") (pinfunction "1_1") (pintype "passive"))
      (node (ref "R8") (pin "2") (pinfunction "2_2") (pintype "passive"))
      (node (ref "U17") (pin "4") (pinfunction "+IN_4") (pintype "input"))
    )
    (net (code "59") (name "Net-(U17--IN)") (class "Default")
      (node (ref "C25") (pin "1") (pinfunction "1_1") (pintype "passive"))
      (node (ref "C26") (pin "2") (pinfunction "2_2") (pintype "passive"))
      (node (ref "R9") (pin "2") (pinfunction "2_2") (pintype "passive"))
      (node (ref "U17") (pin "1") (pinfunction "-IN_1") (pintype "input"))
    )
    (net (code "60") (name "Net-(U17-RG)") (class "Default")
      (node (ref "R10") (pin "1") (pinfunction "1_1") (pintype "passive"))
      (node (ref "U17") (pin "3") (pinfunction "RG_3") (pintype "passive"))
    )
    (net (code "61") (name "Net-(U17-RG_2)") (class "Default")
      (node (ref "R10") (pin "2") (pinfunction "2_2") (pintype "passive"))
      (node (ref "U17") (pin "2") (pinfunction "RG_2_2") (pintype "passive"))
    )
    (net (code "62") (name "Net-(U17-VOUT)") (class "Default")
      (node (ref "R11") (pin "1") (pinfunction "1_1") (pintype "passive"))
      (node (ref "U17") (pin "7") (pinfunction "VOUT_7") (pintype "output"))
    )
    (net (code "63") (name "Net-(X9C-F)") (class "Default")
      (node (ref "R23") (pin "2") (pinfunction "2_2") (pintype "passive"))
      (node (ref "X9") (pin "3") (pinfunction "F_3") (pintype "passive"))
    )
    (net (code "64") (name "Net-(X9D-F)") (class "Default")
      (node (ref "R33") (pin "2") (pinfunction "2_2") (pintype "passive"))
      (node (ref "X9") (pin "4") (pinfunction "F_4") (pintype "passive"))
    )
    (net (code "65") (name "Net-(X9E-F)") (class "Default")
      (node (ref "R34") (pin "2") (pinfunction "2_2") (pintype "passive"))
      (node (ref "X9") (pin "5") (pinfunction "F_5") (pintype "passive"))
    )
    (net (code "66") (name "SDIO_CK") (class "Default")
      (node (ref "U$16") (pin "PIN5") (pinfunction "SCLK_PIN5") (pintype "input"))
      (node (ref "U2") (pin "28") (pinfunction "PB2_28") (pintype "bidirectional"))
    )
    (net (code "67") (name "SDIO_CMD") (class "Default")
      (node (ref "R38") (pin "1") (pinfunction "1_1") (pintype "passive"))
      (node (ref "U$16") (pin "PIN3") (pinfunction "DATA_IN_PIN3") (pintype "input"))
      (node (ref "U2") (pin "54") (pinfunction "PD2_54") (pintype "bidirectional"))
    )
    (net (code "68") (name "SDIO_D0") (class "Default")
      (node (ref "R37") (pin "1") (pinfunction "1_1") (pintype "passive"))
      (node (ref "U$16") (pin "PIN7") (pinfunction "DATA_OUT_PIN7") (pintype "output"))
      (node (ref "U2") (pin "39") (pinfunction "PC8_39") (pintype "bidirectional"))
    )
    (net (code "69") (name "SDIO_D1") (class "Default")
      (node (ref "R40") (pin "1") (pinfunction "1_1") (pintype "passive"))
      (node (ref "U$16") (pin "PIN8") (pinfunction "DAT1_PIN8") (pintype "bidirectional"))
      (node (ref "U2") (pin "26") (pinfunction "PB0_26") (pintype "bidirectional"))
    )
    (net (code "70") (name "SDIO_D2") (class "Default")
      (node (ref "R41") (pin "1") (pinfunction "1_1") (pintype "passive"))
      (node (ref "U$16") (pin "PIN1") (pinfunction "DAT2_PIN1") (pintype "bidirectional"))
      (node (ref "U2") (pin "27") (pinfunction "PB1_27") (pintype "bidirectional"))
    )
    (net (code "71") (name "SDIO_D3") (class "Default")
      (node (ref "R39") (pin "1") (pinfunction "1_1") (pintype "passive"))
      (node (ref "U$16") (pin "PIN2") (pinfunction "CS_PIN2") (pintype "input"))
      (node (ref "U2") (pin "52") (pinfunction "PC11_52") (pintype "bidirectional"))
    )
    (net (code "72") (name "SD_DETECT") (class "Default")
      (node (ref "C21") (pin "1") (pinfunction "1_1") (pintype "passive"))
      (node (ref "R36") (pin "1") (pinfunction "1_1") (pintype "passive"))
      (node (ref "U2") (pin "38") (pinfunction "PC7_38") (pintype "bidirectional"))
    )
    (net (code "73") (name "SERVO1_PWM") (class "Default")
      (node (ref "R23") (pin "1") (pinfunction "1_1") (pintype "passive"))
      (node (ref "U2") (pin "56") (pinfunction "PB4_56") (pintype "bidirectional"))
    )
    (net (code "74") (name "SERVO2_PWM") (class "Default")
      (node (ref "R33") (pin "1") (pinfunction "1_1") (pintype "passive"))
      (node (ref "U2") (pin "61") (pinfunction "PB8_61") (pintype "bidirectional"))
    )
    (net (code "75") (name "SERVO3_PWM") (class "Default")
      (node (ref "R34") (pin "1") (pinfunction "1_1") (pintype "passive"))
      (node (ref "U2") (pin "62") (pinfunction "PB9_62") (pintype "bidirectional"))
    )
    (net (code "76") (name "SWCLK") (class "Default")
      (node (ref "U2") (pin "49") (pinfunction "PA14_49") (pintype "bidirectional"))
      (node (ref "X1") (pin "3") (pinfunction "S_3") (pintype "passive"))
    )
    (net (code "77") (name "SWDIO") (class "Default")
      (node (ref "U2") (pin "46") (pinfunction "PA13_46") (pintype "bidirectional"))
      (node (ref "X1") (pin "4") (pinfunction "S_4") (pintype "passive"))
    )
    (net (code "78") (name "TENSO_ADC") (class "Default")
      (node (ref "C28") (pin "1") (pinfunction "1_1") (pintype "passive"))
      (node (ref "R11") (pin "2") (pinfunction "2_2") (pintype "passive"))
      (node (ref "U2") (pin "8") (pinfunction "PC0_8") (pintype "bidirectional"))
    )
    (net (code "79") (name "TENSO_IN+") (class "Default")
      (node (ref "R8") (pin "1") (pinfunction "1_1") (pintype "passive"))
      (node (ref "X9") (pin "6") (pinfunction "F_6") (pintype "passive"))
    )
    (net (code "80") (name "TENSO_IN-") (class "Default")
      (node (ref "R9") (pin "1") (pinfunction "1_1") (pintype "passive"))
      (node (ref "X9") (pin "7") (pinfunction "F_7") (pintype "passive"))
    )
    (net (code "81") (name "UART_RX") (class "Default")
      (node (ref "U2") (pin "17") (pinfunction "PA3_17") (pintype "bidirectional"))
      (node (ref "X2") (pin "2") (pinfunction "S_2") (pintype "passive"))
    )
    (net (code "82") (name "UART_TX") (class "Default")
      (node (ref "U2") (pin "16") (pinfunction "PA2_16") (pintype "bidirectional"))
      (node (ref "X2") (pin "3") (pinfunction "S_3") (pintype "passive"))
    )
    (net (code "83") (name "XBEE_RX") (class "Default")
      (node (ref "U$1") (pin "2") (pinfunction "DOUT_2") (pintype "output"))
      (node (ref "U2") (pin "43") (pinfunction "PA10_43") (pintype "bidirectional"))
    )
    (net (code "84") (name "XBEE_TX") (class "Default")
      (node (ref "U$1") (pin "3") (pinfunction "DIN_3") (pintype "input"))
      (node (ref "U2") (pin "42") (pinfunction "PA9_42") (pintype "bidirectional"))
    )
    (net (code "85") (name "XBEE_VDD") (class "Default")
      (node (ref "C13") (pin "+") (pinfunction "+_+") (pintype "passive"))
      (node (ref "C30") (pin "1") (pinfunction "1_1") (pintype "passive"))
      (node (ref "IC1") (pin "2") (pinfunction "OUT_2") (pintype "passive"))
      (node (ref "U$1") (pin "1") (pinfunction "VDD_1") (pintype "power_in"))
    )
    (net (code "86") (name "unconnected-(U$1-CTS-Pad12)") (class "Default")
      (node (ref "U$1") (pin "12") (pinfunction "CTS_12") (pintype "output"))
    )
    (net (code "87") (name "unconnected-(U$1-DIO0-Pad20)") (class "Default")
      (node (ref "U$1") (pin "20") (pinfunction "DIO0_20") (pintype "bidirectional"))
    )
    (net (code "88") (name "unconnected-(U$1-DIO1-Pad19)") (class "Default")
      (node (ref "U$1") (pin "19") (pinfunction "DIO1_19") (pintype "bidirectional"))
    )
    (net (code "89") (name "unconnected-(U$1-DIO2-Pad18)") (class "Default")
      (node (ref "U$1") (pin "18") (pinfunction "DIO2_18") (pintype "bidirectional"))
    )
    (net (code "90") (name "unconnected-(U$1-DIO3-Pad17)") (class "Default")
      (node (ref "U$1") (pin "17") (pinfunction "DIO3_17") (pintype "bidirectional"))
    )
    (net (code "91") (name "unconnected-(U$1-DIO4-Pad11)") (class "Default")
      (node (ref "U$1") (pin "11") (pinfunction "DIO4_11") (pintype "bidirectional"))
    )
    (net (code "92") (name "unconnected-(U$1-DIO9-Pad13)") (class "Default")
      (node (ref "U$1") (pin "13") (pinfunction "DIO9_13") (pintype "bidirectional"))
    )
    (net (code "93") (name "unconnected-(U$1-DIO11-Pad7)") (class "Default")
      (node (ref "U$1") (pin "7") (pinfunction "DIO11_7") (pintype "bidirectional"))
    )
    (net (code "94") (name "unconnected-(U$1-DIO12-Pad4)") (class "Default")
      (node (ref "U$1") (pin "4") (pinfunction "DIO12_4") (pintype "bidirectional"))
    )
    (net (code "95") (name "unconnected-(U$1-DTR-Pad9)") (class "Default")
      (node (ref "U$1") (pin "9") (pinfunction "DTR_9") (pintype "bidirectional"))
    )
    (net (code "96") (name "unconnected-(U$1-RES-Pad8)") (class "Default")
      (node (ref "U$1") (pin "8") (pinfunction "RES_8") (pintype "bidirectional"))
    )
    (net (code "97") (name "unconnected-(U$1-RES-Pad14)") (class "Default")
      (node (ref "U$1") (pin "14") (pinfunction "RES_14") (pintype "bidirectional"))
    )
    (net (code "98") (name "unconnected-(U$1-RTS-Pad16)") (class "Default")
      (node (ref "U$1") (pin "16") (pinfunction "RTS_16") (pintype "input"))
    )
    (net (code "99") (name "unconnected-(U$10-PadP$1)") (class "Default")
      (node (ref "U$10") (pin "P$1") (pinfunction "P$1_P$1") (pintype "bidirectional"))
    )
    (net (code "100") (name "unconnected-(U$11-IO3{slash}~{RESET}-Pad1)") (class "Default")
      (node (ref "U$11") (pin "1") (pinfunction "IO3/~{RESET}_1") (pintype "bidirectional"))
    )
    (net (code "101") (name "unconnected-(U$11-~{WP}-Pad9)") (class "Default")
      (node (ref "U$11") (pin "9") (pinfunction "~{WP}_9") (pintype "bidirectional"))
    )
    (net (code "102") (name "unconnected-(U1-VREF-Pad5)") (class "Default")
      (node (ref "U1") (pin "5") (pinfunction "VREF_5") (pintype "output"))
    )
    (net (code "103") (name "unconnected-(U2-PA0-Pad14)") (class "Default")
      (node (ref "U2") (pin "14") (pinfunction "PA0_14") (pintype "bidirectional"))
    )
    (net (code "104") (name "unconnected-(U2-PA1-Pad15)") (class "Default")
      (node (ref "U2") (pin "15") (pinfunction "PA1_15") (pintype "bidirectional"))
    )
    (net (code "105") (name "unconnected-(U2-PA8-Pad41)") (class "Default")
      (node (ref "U2") (pin "41") (pinfunction "PA8_41") (pintype "bidirectional"))
    )
    (net (code "106") (name "unconnected-(U2-PA15-Pad50)") (class "Default")
      (node (ref "U2") (pin "50") (pinfunction "PA15_50") (pintype "bidirectional"))
    )
    (net (code "107") (name "unconnected-(U2-PB6-Pad58)") (class "Default")
      (node (ref "U2") (pin "58") (pinfunction "PB6_58") (pintype "bidirectional"))
    )
    (net (code "108") (name "unconnected-(U2-PB10-Pad29)") (class "Default")
      (node (ref "U2") (pin "29") (pinfunction "PB10_29") (pintype "bidirectional"))
    )
    (net (code "109") (name "unconnected-(U2-PC2-Pad10)") (class "Default")
      (node (ref "U2") (pin "10") (pinfunction "PC2_10") (pintype "bidirectional"))
    )
    (net (code "110") (name "unconnected-(U2-PC3-Pad11)") (class "Default")
      (node (ref "U2") (pin "11") (pinfunction "PC3_11") (pintype "bidirectional"))
    )
    (net (code "111") (name "unconnected-(U2-PC4-Pad24)") (class "Default")
      (node (ref "U2") (pin "24") (pinfunction "PC4_24") (pintype "bidirectional"))
    )
    (net (code "112") (name "unconnected-(U2-PC9-Pad40)") (class "Default")
      (node (ref "U2") (pin "40") (pinfunction "PC9_40") (pintype "bidirectional"))
    )
    (net (code "113") (name "unconnected-(U2-PC13-Pad2)") (class "Default")
      (node (ref "U2") (pin "2") (pinfunction "PC13_2") (pintype "bidirectional"))
    )
    (net (code "114") (name "unconnected-(U2-PC14-OSC32_IN-Pad3)") (class "Default")
      (node (ref "U2") (pin "3") (pinfunction "PC14-OSC32_IN_3") (pintype "bidirectional"))
    )
    (net (code "115") (name "unconnected-(U2-PC15-OSC32_OUT-Pad4)") (class "Default")
      (node (ref "U2") (pin "4") (pinfunction "PC15-OSC32_OUT_4") (pintype "bidirectional"))
    )
    (net (code "116") (name "unconnected-(X8D-S-Pad4)") (class "Default")
      (node (ref "X8") (pin "4") (pinfunction "S_4") (pintype "passive"))
    )
  )
)
